# Sheet1.net
KiCad netlist of a schematic drawn in Altium Designer
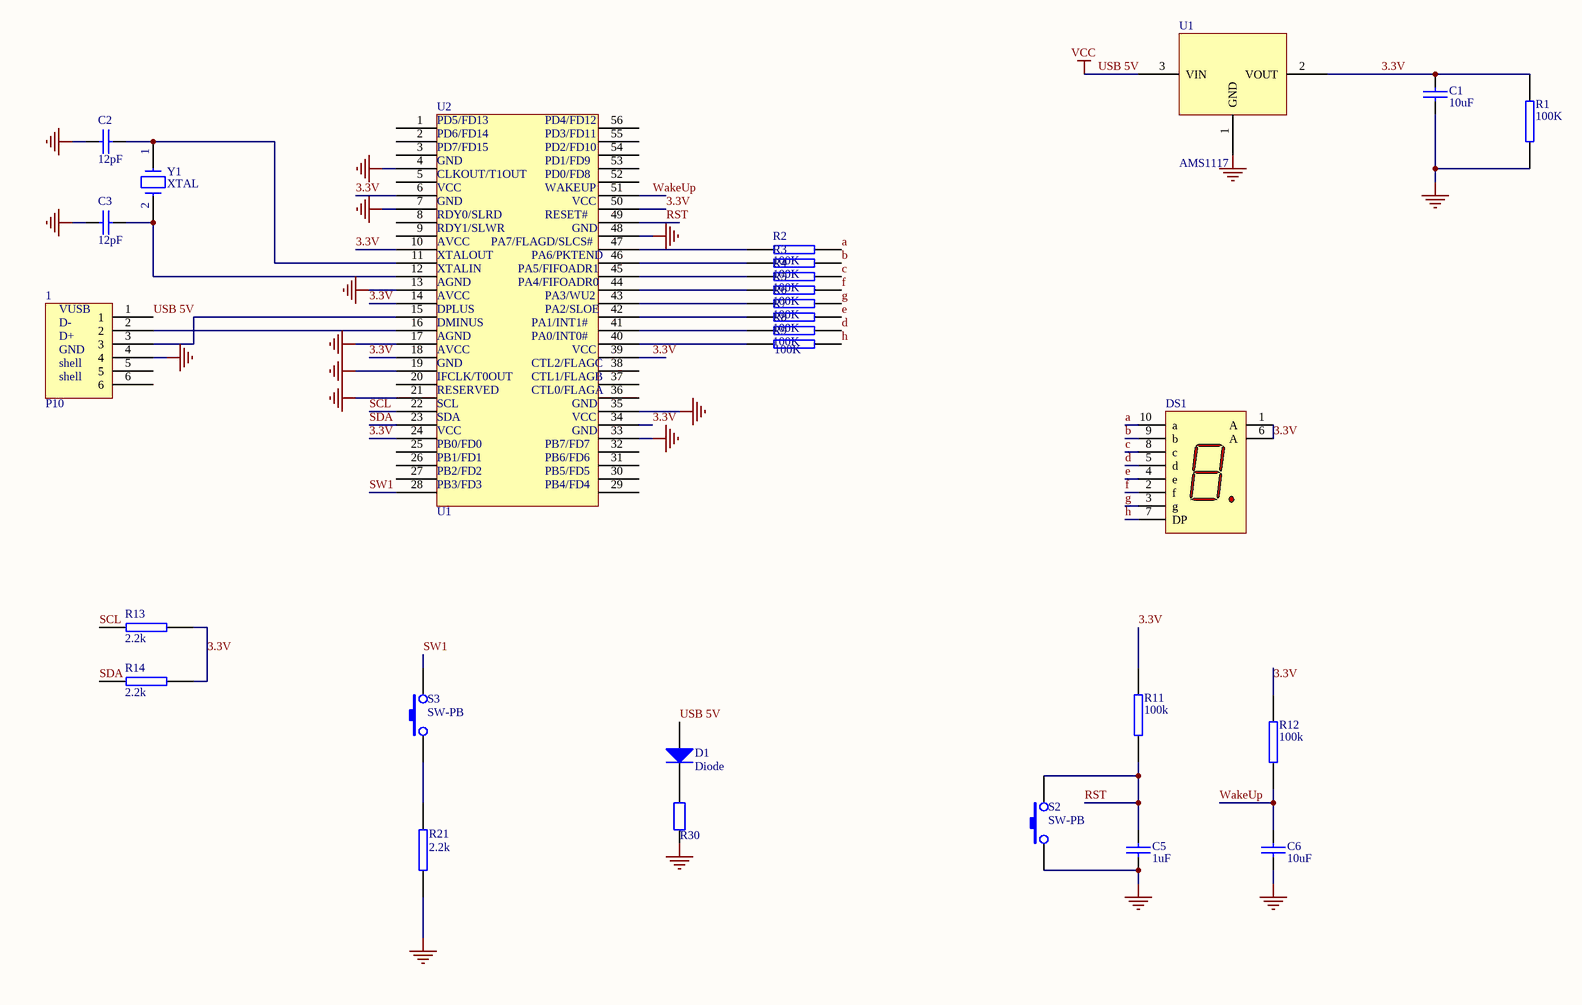
[diagram p0: Sheet1.SchDoc]

(export (version "E")
  (design (tool "Eeschema 10.0.6"))
  (components
    (comp (ref "1") (value "P10") (footprint "787616") (libsource (lib "USBHeader") (part "COMPONENT_1")))
    (comp (ref "C1")
      (value "10uF")
      (footprint "0805")
      (description "Capacitor")
      (libsource (lib "*") (part "CAP"))
    )
    (comp (ref "C2")
      (value "12pF")
      (footprint "0805")
      (description "Capacitor")
      (libsource (lib "*") (part "CAP"))
    )
    (comp (ref "C3")
      (value "12pF")
      (footprint "0805")
      (description "Capacitor")
      (libsource (lib "*") (part "CAP"))
    )
    (comp (ref "C5")
      (value "1uF")
      (footprint "0805")
      (description "Capacitor")
      (libsource (lib "*") (part "CAP"))
    )
    (comp (ref "C6")
      (value "10uF")
      (footprint "0805")
      (description "Capacitor")
      (libsource (lib "*") (part "CAP"))
    )
    (comp (ref "D1")
      (value "Diode")
      (footprint "0805")
      (description "Default Diode")
      (fields (field (name "PUBLISHER") "Altium Limited"))
      (libsource (lib "Miscellaneous Devices") (part "Diode"))
    )
    (comp (ref "DS1")
      (value "Dpy Red-CA")
      (footprint "LEDDIP-10")
      (description "7.62 mm Black Surface HER 7-Segment Display: CA, RH DP")
      (fields (field (name "PUBLISHER") "Altium Limited"))
      (libsource (lib "Miscellaneous Devices") (part "Dpy Red-CA"))
    )
    (comp (ref "R1") (value "100K") (footprint "0805") (libsource (lib "*") (part "RES2")))
    (comp (ref "R2") (value "100K") (footprint "0805") (libsource (lib "*") (part "RES2")))
    (comp (ref "R3") (value "100K") (footprint "0805") (libsource (lib "*") (part "RES2")))
    (comp (ref "R4") (value "100K") (footprint "0805") (libsource (lib "*") (part "RES2")))
    (comp (ref "R5") (value "100K") (footprint "0805") (libsource (lib "*") (part "RES2")))
    (comp (ref "R6") (value "100K") (footprint "0805") (libsource (lib "*") (part "RES2")))
    (comp (ref "R7") (value "100K") (footprint "0805") (libsource (lib "*") (part "RES2")))
    (comp (ref "R8") (value "100K") (footprint "0805") (libsource (lib "*") (part "RES2")))
    (comp (ref "R9") (value "100K") (footprint "0805") (libsource (lib "*") (part "RES2")))
    (comp (ref "R11") (value "100k") (footprint "0805") (libsource (lib "*") (part "RES2")))
    (comp (ref "R12") (value "100k") (footprint "0805") (libsource (lib "*") (part "RES2")))
    (comp (ref "R13") (value "2.2k") (footprint "0805") (libsource (lib "*") (part "RES2")))
    (comp (ref "R14") (value "2.2k") (footprint "0805") (libsource (lib "*") (part "RES2")))
    (comp (ref "R21") (value "2.2k") (footprint "0805") (libsource (lib "*") (part "RES2")))
    (comp (ref "R30")
      (value "Res2")
      (footprint "0805")
      (description "Resistor")
      (fields (field (name "PUBLISHER") "Altium Limited"))
      (libsource (lib "Miscellaneous Devices") (part "Res2"))
    )
    (comp (ref "S2") (value "SW-PB") (footprint "SW2") (libsource (lib "*") (part "SW-PB")))
    (comp (ref "S3") (value "SW-PB") (footprint "SW2") (libsource (lib "*") (part "SW-PB")))
    (comp (ref "U1")
      (value "AMS1117")
      (footprint "SOT223")
      (libsource (lib "USBHeader") (part "COMPONENT_2"))
    )
    (comp (ref "U2") (value "U1") (footprint "SOP56 -1") (libsource (lib "68013") (part "Component_1")))
    (comp (ref "Y1")
      (value "XTAL")
      (footprint "RAD-0.2")
      (description "Crystal")
      (libsource (lib "*") (part "CRYSTAL"))
    )
  )
  (nets
    (net (code "1") (name "/3.3V") (class "Default")
      (node (ref "C1") (pin "2") (pinfunction "2_2") (pintype "passive"))
      (node (ref "DS1") (pin "1") (pinfunction "A_1") (pintype "passive"))
      (node (ref "DS1") (pin "6") (pinfunction "A_6") (pintype "passive"))
      (node (ref "R1") (pin "2") (pinfunction "2_2") (pintype "passive"))
      (node (ref "R11") (pin "2") (pinfunction "2_2") (pintype "passive"))
      (node (ref "R12") (pin "2") (pinfunction "2_2") (pintype "passive"))
      (node (ref "R13") (pin "2") (pinfunction "2_2") (pintype "passive"))
      (node (ref "R14") (pin "2") (pinfunction "2_2") (pintype "passive"))
      (node (ref "U1") (pin "2") (pinfunction "VOUT_2") (pintype "passive"))
      (node (ref "U2") (pin "10") (pintype "passive"))
      (node (ref "U2") (pin "14") (pintype "passive"))
      (node (ref "U2") (pin "18") (pintype "passive"))
      (node (ref "U2") (pin "24") (pintype "passive"))
      (node (ref "U2") (pin "34") (pintype "passive"))
      (node (ref "U2") (pin "39") (pintype "passive"))
      (node (ref "U2") (pin "50") (pintype "passive"))
      (node (ref "U2") (pin "6") (pintype "passive"))
    )
    (net (code "2") (name "/RST") (class "Default")
      (node (ref "C5") (pin "2") (pinfunction "2_2") (pintype "passive"))
      (node (ref "R11") (pin "1") (pinfunction "1_1") (pintype "passive"))
      (node (ref "S2") (pin "2") (pinfunction "2_2") (pintype "passive"))
      (node (ref "U2") (pin "49") (pintype "passive"))
    )
    (net (code "3") (name "/SCL") (class "Default")
      (node (ref "R13") (pin "1") (pinfunction "1_1") (pintype "passive"))
      (node (ref "U2") (pin "22") (pintype "passive"))
    )
    (net (code "4") (name "/SDA") (class "Default")
      (node (ref "R14") (pin "1") (pinfunction "1_1") (pintype "passive"))
      (node (ref "U2") (pin "23") (pintype "passive"))
    )
    (net (code "5") (name "/SW1") (class "Default")
      (node (ref "S3") (pin "2") (pinfunction "2_2") (pintype "passive"))
      (node (ref "U2") (pin "28") (pintype "passive"))
    )
    (net (code "6") (name "/WakeUp") (class "Default")
      (node (ref "C6") (pin "2") (pinfunction "2_2") (pintype "passive"))
      (node (ref "R12") (pin "1") (pinfunction "1_1") (pintype "passive"))
      (node (ref "U2") (pin "51") (pintype "passive"))
    )
    (net (code "7") (name "/a") (class "Default")
      (node (ref "DS1") (pin "10") (pinfunction "a_10") (pintype "passive"))
      (node (ref "R2") (pin "1") (pinfunction "1_1") (pintype "passive"))
    )
    (net (code "8") (name "/b") (class "Default")
      (node (ref "DS1") (pin "9") (pinfunction "b_9") (pintype "passive"))
      (node (ref "R3") (pin "1") (pinfunction "1_1") (pintype "passive"))
    )
    (net (code "9") (name "/c") (class "Default")
      (node (ref "DS1") (pin "8") (pinfunction "c_8") (pintype "passive"))
      (node (ref "R4") (pin "1") (pinfunction "1_1") (pintype "passive"))
    )
    (net (code "10") (name "/d") (class "Default")
      (node (ref "DS1") (pin "5") (pinfunction "d_5") (pintype "passive"))
      (node (ref "R8") (pin "1") (pinfunction "1_1") (pintype "passive"))
    )
    (net (code "11") (name "/e") (class "Default")
      (node (ref "DS1") (pin "4") (pinfunction "e_4") (pintype "passive"))
      (node (ref "R7") (pin "1") (pinfunction "1_1") (pintype "passive"))
    )
    (net (code "12") (name "/f") (class "Default")
      (node (ref "DS1") (pin "2") (pinfunction "f_2") (pintype "passive"))
      (node (ref "R5") (pin "1") (pinfunction "1_1") (pintype "passive"))
    )
    (net (code "13") (name "/g") (class "Default")
      (node (ref "DS1") (pin "3") (pinfunction "g_3") (pintype "passive"))
      (node (ref "R6") (pin "1") (pinfunction "1_1") (pintype "passive"))
    )
    (net (code "14") (name "/h") (class "Default")
      (node (ref "DS1") (pin "7") (pinfunction "DP_7") (pintype "passive"))
      (node (ref "R9") (pin "1") (pinfunction "1_1") (pintype "passive"))
    )
    (net (code "15") (name "GND") (class "Default")
      (node (ref "1") (pin "4") (pinfunction "4_4") (pintype "passive"))
      (node (ref "C1") (pin "1") (pinfunction "1_1") (pintype "passive"))
      (node (ref "C2") (pin "1") (pinfunction "1_1") (pintype "passive"))
      (node (ref "C3") (pin "1") (pinfunction "1_1") (pintype "passive"))
      (node (ref "C5") (pin "1") (pinfunction "1_1") (pintype "passive"))
      (node (ref "C6") (pin "1") (pinfunction "1_1") (pintype "passive"))
      (node (ref "R1") (pin "1") (pinfunction "1_1") (pintype "passive"))
      (node (ref "R21") (pin "1") (pinfunction "1_1") (pintype "passive"))
      (node (ref "R30") (pin "2") (pinfunction "2_2") (pintype "passive"))
      (node (ref "S2") (pin "1") (pinfunction "1_1") (pintype "passive"))
      (node (ref "U1") (pin "1") (pinfunction "GND_1") (pintype "passive"))
      (node (ref "U2") (pin "13") (pintype "passive"))
      (node (ref "U2") (pin "17") (pintype "passive"))
      (node (ref "U2") (pin "19") (pintype "passive"))
      (node (ref "U2") (pin "21") (pintype "passive"))
      (node (ref "U2") (pin "33") (pintype "passive"))
      (node (ref "U2") (pin "35") (pintype "passive"))
      (node (ref "U2") (pin "4") (pintype "passive"))
      (node (ref "U2") (pin "48") (pintype "passive"))
      (node (ref "U2") (pin "7") (pintype "passive"))
    )
    (net (code "16") (name "Net-(1-Pad2)") (class "Default")
      (node (ref "1") (pin "2") (pinfunction "2_2") (pintype "passive"))
      (node (ref "U2") (pin "16") (pintype "passive"))
    )
    (net (code "17") (name "Net-(1-Pad3)") (class "Default")
      (node (ref "1") (pin "3") (pinfunction "3_3") (pintype "passive"))
      (node (ref "U2") (pin "15") (pintype "passive"))
    )
    (net (code "18") (name "Net-(C2-Pad2)") (class "Default")
      (node (ref "C2") (pin "2") (pinfunction "2_2") (pintype "passive"))
      (node (ref "U2") (pin "11") (pintype "passive"))
      (node (ref "Y1") (pin "1") (pinfunction "1_1") (pintype "passive"))
    )
    (net (code "19") (name "Net-(C3-Pad2)") (class "Default")
      (node (ref "C3") (pin "2") (pinfunction "2_2") (pintype "passive"))
      (node (ref "U2") (pin "12") (pintype "passive"))
      (node (ref "Y1") (pin "2") (pinfunction "2_2") (pintype "passive"))
    )
    (net (code "20") (name "Net-(D1-K)") (class "Default")
      (node (ref "D1") (pin "2") (pinfunction "K_2") (pintype "passive"))
      (node (ref "R30") (pin "1") (pinfunction "1_1") (pintype "passive"))
    )
    (net (code "21") (name "Net-(R2-Pad2)") (class "Default")
      (node (ref "R2") (pin "2") (pinfunction "2_2") (pintype "passive"))
      (node (ref "U2") (pin "47") (pintype "passive"))
    )
    (net (code "22") (name "Net-(R3-Pad2)") (class "Default")
      (node (ref "R3") (pin "2") (pinfunction "2_2") (pintype "passive"))
      (node (ref "U2") (pin "46") (pintype "passive"))
    )
    (net (code "23") (name "Net-(R4-Pad2)") (class "Default")
      (node (ref "R4") (pin "2") (pinfunction "2_2") (pintype "passive"))
      (node (ref "U2") (pin "45") (pintype "passive"))
    )
    (net (code "24") (name "Net-(R5-Pad2)") (class "Default")
      (node (ref "R5") (pin "2") (pinfunction "2_2") (pintype "passive"))
      (node (ref "U2") (pin "44") (pintype "passive"))
    )
    (net (code "25") (name "Net-(R6-Pad2)") (class "Default")
      (node (ref "R6") (pin "2") (pinfunction "2_2") (pintype "passive"))
      (node (ref "U2") (pin "43") (pintype "passive"))
    )
    (net (code "26") (name "Net-(R7-Pad2)") (class "Default")
      (node (ref "R7") (pin "2") (pinfunction "2_2") (pintype "passive"))
      (node (ref "U2") (pin "42") (pintype "passive"))
    )
    (net (code "27") (name "Net-(R8-Pad2)") (class "Default")
      (node (ref "R8") (pin "2") (pinfunction "2_2") (pintype "passive"))
      (node (ref "U2") (pin "41") (pintype "passive"))
    )
    (net (code "28") (name "Net-(R9-Pad2)") (class "Default")
      (node (ref "R9") (pin "2") (pinfunction "2_2") (pintype "passive"))
      (node (ref "U2") (pin "40") (pintype "passive"))
    )
    (net (code "29") (name "Net-(R21-Pad2)") (class "Default")
      (node (ref "R21") (pin "2") (pinfunction "2_2") (pintype "passive"))
      (node (ref "S3") (pin "1") (pinfunction "1_1") (pintype "passive"))
    )
    (net (code "30") (name "VCC") (class "Default")
      (node (ref "1") (pin "1") (pinfunction "1_1") (pintype "passive"))
      (node (ref "D1") (pin "1") (pinfunction "A_1") (pintype "passive"))
      (node (ref "U1") (pin "3") (pinfunction "VIN_3") (pintype "passive"))
    )
    (net (code "31") (name "unconnected-(1-Pad5)") (class "Default")
      (node (ref "1") (pin "5") (pinfunction "5_5") (pintype "passive"))
    )
    (net (code "32") (name "unconnected-(1-Pad6)") (class "Default")
      (node (ref "1") (pin "6") (pinfunction "6_6") (pintype "passive"))
    )
    (net (code "33") (name "unconnected-(U2-Pad1)") (class "Default")
      (node (ref "U2") (pin "1") (pintype "passive"))
    )
    (net (code "34") (name "unconnected-(U2-Pad2)") (class "Default")
      (node (ref "U2") (pin "2") (pintype "passive"))
    )
    (net (code "35") (name "unconnected-(U2-Pad3)") (class "Default")
      (node (ref "U2") (pin "3") (pintype "passive"))
    )
    (net (code "36") (name "unconnected-(U2-Pad5)") (class "Default")
      (node (ref "U2") (pin "5") (pintype "passive"))
    )
    (net (code "37") (name "unconnected-(U2-Pad8)") (class "Default")
      (node (ref "U2") (pin "8") (pintype "passive"))
    )
    (net (code "38") (name "unconnected-(U2-Pad9)") (class "Default")
      (node (ref "U2") (pin "9") (pintype "passive"))
    )
    (net (code "39") (name "unconnected-(U2-Pad20)") (class "Default")
      (node (ref "U2") (pin "20") (pintype "passive"))
    )
    (net (code "40") (name "unconnected-(U2-Pad25)") (class "Default")
      (node (ref "U2") (pin "25") (pintype "passive"))
    )
    (net (code "41") (name "unconnected-(U2-Pad26)") (class "Default")
      (node (ref "U2") (pin "26") (pintype "passive"))
    )
    (net (code "42") (name "unconnected-(U2-Pad27)") (class "Default")
      (node (ref "U2") (pin "27") (pintype "passive"))
    )
    (net (code "43") (name "unconnected-(U2-Pad29)") (class "Default")
      (node (ref "U2") (pin "29") (pintype "passive"))
    )
    (net (code "44") (name "unconnected-(U2-Pad30)") (class "Default")
      (node (ref "U2") (pin "30") (pintype "passive"))
    )
    (net (code "45") (name "unconnected-(U2-Pad31)") (class "Default")
      (node (ref "U2") (pin "31") (pintype "passive"))
    )
    (net (code "46") (name "unconnected-(U2-Pad32)") (class "Default")
      (node (ref "U2") (pin "32") (pintype "passive"))
    )
    (net (code "47") (name "unconnected-(U2-Pad36)") (class "Default")
      (node (ref "U2") (pin "36") (pintype "passive"))
    )
    (net (code "48") (name "unconnected-(U2-Pad37)") (class "Default")
      (node (ref "U2") (pin "37") (pintype "passive"))
    )
    (net (code "49") (name "unconnected-(U2-Pad38)") (class "Default")
      (node (ref "U2") (pin "38") (pintype "passive"))
    )
    (net (code "50") (name "unconnected-(U2-Pad52)") (class "Default")
      (node (ref "U2") (pin "52") (pintype "passive"))
    )
    (net (code "51") (name "unconnected-(U2-Pad53)") (class "Default")
      (node (ref "U2") (pin "53") (pintype "passive"))
    )
    (net (code "52") (name "unconnected-(U2-Pad54)") (class "Default")
      (node (ref "U2") (pin "54") (pintype "passive"))
    )
    (net (code "53") (name "unconnected-(U2-Pad55)") (class "Default")
      (node (ref "U2") (pin "55") (pintype "passive"))
    )
    (net (code "54") (name "unconnected-(U2-Pad56)") (class "Default")
      (node (ref "U2") (pin "56") (pintype "passive"))
    )
  )
)
